# iotchair_nano-shield.net
KiCad netlist of a schematic drawn in EAGLE
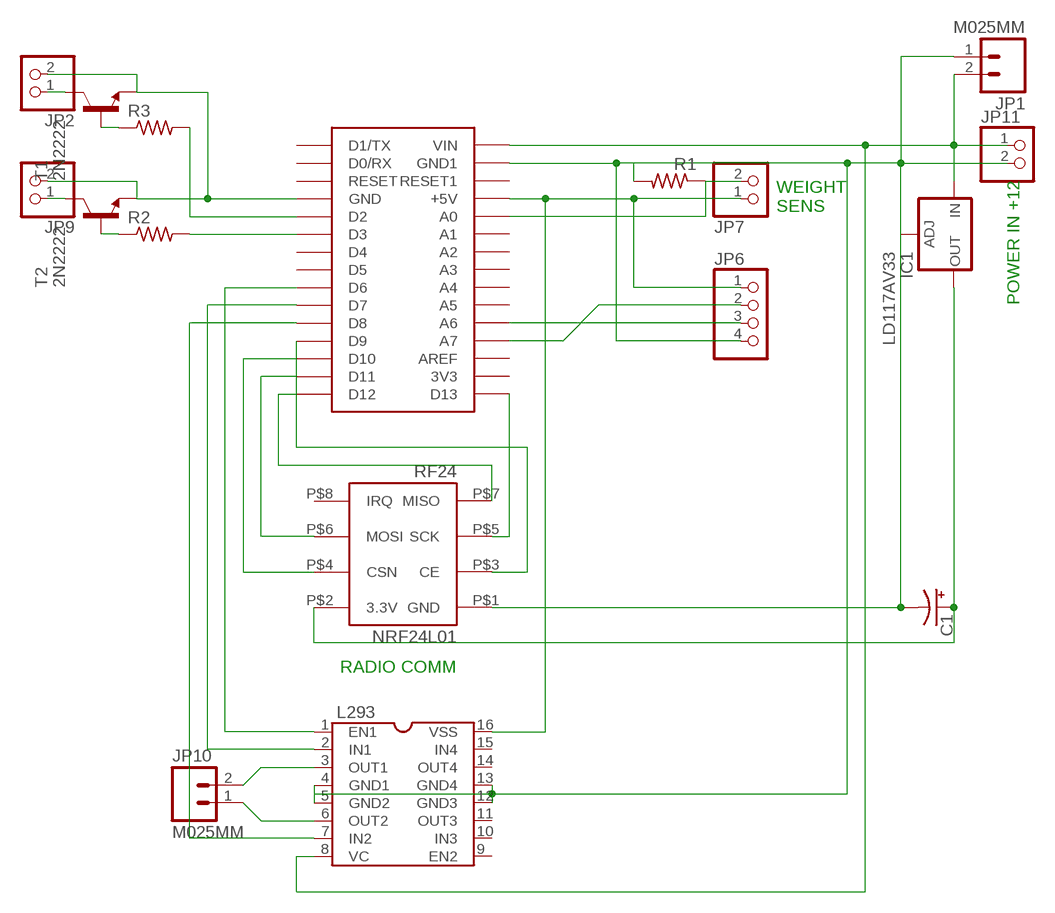
[diagram p0: schematic, sheet 1]

(export (version "E")
  (design (tool "Eeschema 10.0.6"))
  (components
    (comp (ref "C1")
      (value "CPOL-USTT2D6L")
      (footprint "eagle-import:TT2D6L")
      (libsource (lib "eagle-import") (part "CPOL-USTT2D6L"))
    )
    (comp (ref "IC1")
      (value "LD117AV33")
      (footprint "eagle-import:TO220L1")
      (libsource (lib "eagle-import") (part "LD117A?V33"))
    )
    (comp (ref "JP1")
      (value "M025MM")
      (footprint "eagle-import:SCREWTERMINAL-5MM-2")
      (libsource (lib "eagle-import") (part "M025MM"))
    )
    (comp (ref "JP2")
      (value "PINHD-1X2")
      (footprint "eagle-import:1X02")
      (libsource (lib "eagle-import") (part "PINHD-1X2"))
    )
    (comp (ref "JP6")
      (value "PINHD-1X4")
      (footprint "eagle-import:1X04")
      (libsource (lib "eagle-import") (part "PINHD-1X4"))
    )
    (comp (ref "JP7")
      (value "PINHD-1X2")
      (footprint "eagle-import:1X02")
      (libsource (lib "eagle-import") (part "PINHD-1X2"))
    )
    (comp (ref "JP9")
      (value "PINHD-1X2")
      (footprint "eagle-import:1X02")
      (libsource (lib "eagle-import") (part "PINHD-1X2"))
    )
    (comp (ref "JP10")
      (value "M025MM")
      (footprint "eagle-import:SCREWTERMINAL-5MM-2")
      (libsource (lib "eagle-import") (part "M025MM"))
    )
    (comp (ref "JP11")
      (value "PINHD-1X2")
      (footprint "eagle-import:1X02")
      (libsource (lib "eagle-import") (part "PINHD-1X2"))
    )
    (comp (ref "L293")
      (value "DIL16")
      (footprint "eagle-import:DIL16")
      (libsource (lib "eagle-import") (part "DIL16"))
    )
    (comp (ref "NRF24L01")
      (value "RF24")
      (footprint "eagle-import:4X2HEADER")
      (libsource (lib "eagle-import") (part "RF24"))
    )
    (comp (ref "R1")
      (value "R-US_0204/5")
      (footprint "eagle-import:0204_5")
      (libsource (lib "eagle-import") (part "R-US_0204/5"))
    )
    (comp (ref "R2")
      (value "R-US_0204/5")
      (footprint "eagle-import:0204_5")
      (libsource (lib "eagle-import") (part "R-US_0204/5"))
    )
    (comp (ref "R3")
      (value "R-US_0204/5")
      (footprint "eagle-import:0204_5")
      (libsource (lib "eagle-import") (part "R-US_0204/5"))
    )
    (comp (ref "T1")
      (value "2N2222")
      (footprint "eagle-import:TO92-EBC-OVAL")
      (libsource (lib "eagle-import") (part "2N2222"))
    )
    (comp (ref "T2")
      (value "2N2222")
      (footprint "eagle-import:TO92-EBC-OVAL")
      (libsource (lib "eagle-import") (part "2N2222"))
    )
    (comp (ref "U$1")
      (value "ARDUINONANO")
      (footprint "eagle-import:PDIP-32")
      (libsource (lib "eagle-import") (part "ARDUINONANO"))
    )
  )
  (nets
    (net (code "1") (name "Net-(IC1-ADJ)") (class "Default")
      (node (ref "C1") (pin "-") (pinfunction "-_-") (pintype "passive"))
      (node (ref "IC1") (pin "1") (pinfunction "ADJ_1") (pintype "input"))
      (node (ref "JP1") (pin "1") (pinfunction "1_1") (pintype "passive"))
      (node (ref "JP11") (pin "2") (pinfunction "2_2") (pintype "passive"))
      (node (ref "JP6") (pin "4") (pinfunction "4_4") (pintype "passive"))
      (node (ref "L293") (pin "12") (pinfunction "GND3_12") (pintype "passive"))
      (node (ref "L293") (pin "13") (pinfunction "GND4_13") (pintype "passive"))
      (node (ref "L293") (pin "4") (pinfunction "GND1_4") (pintype "passive"))
      (node (ref "L293") (pin "5") (pinfunction "GND2_5") (pintype "passive"))
      (node (ref "NRF24L01") (pin "P$1") (pinfunction "GND_P$1") (pintype "bidirectional"))
      (node (ref "R1") (pin "2") (pinfunction "2_2") (pintype "passive"))
      (node (ref "U$1") (pin "GND1") (pinfunction "GND1_GND1") (pintype "bidirectional"))
    )
    (net (code "2") (name "Net-(IC1-IN)") (class "Default")
      (node (ref "IC1") (pin "3") (pinfunction "IN_3") (pintype "input"))
      (node (ref "JP1") (pin "2") (pinfunction "2_2") (pintype "passive"))
      (node (ref "JP11") (pin "1") (pinfunction "1_1") (pintype "passive"))
      (node (ref "L293") (pin "8") (pinfunction "VC_8") (pintype "passive"))
      (node (ref "U$1") (pin "VIN") (pinfunction "VIN_VIN") (pintype "bidirectional"))
    )
    (net (code "3") (name "Net-(IC1-OUT)") (class "Default")
      (node (ref "C1") (pin "+") (pinfunction "+_+") (pintype "passive"))
      (node (ref "IC1") (pin "2") (pinfunction "OUT_2") (pintype "passive"))
      (node (ref "NRF24L01") (pin "P$2") (pinfunction "3.3V_P$2") (pintype "bidirectional"))
    )
    (net (code "4") (name "Net-(JP2-Pad1)") (class "Default")
      (node (ref "JP2") (pin "1") (pinfunction "1_1") (pintype "passive"))
      (node (ref "T1") (pin "C") (pinfunction "C_C") (pintype "passive"))
    )
    (net (code "5") (name "Net-(JP2-Pad2)") (class "Default")
      (node (ref "JP2") (pin "2") (pinfunction "2_2") (pintype "passive"))
      (node (ref "JP9") (pin "2") (pinfunction "2_2") (pintype "passive"))
      (node (ref "T1") (pin "E") (pinfunction "E_E") (pintype "passive"))
      (node (ref "T2") (pin "E") (pinfunction "E_E") (pintype "passive"))
      (node (ref "U$1") (pin "GND") (pinfunction "GND_GND") (pintype "bidirectional"))
    )
    (net (code "6") (name "Net-(JP6-Pad2)") (class "Default")
      (node (ref "JP6") (pin "2") (pinfunction "2_2") (pintype "passive"))
      (node (ref "U$1") (pin "A7") (pinfunction "A7_A7") (pintype "bidirectional"))
    )
    (net (code "7") (name "Net-(JP6-Pad3)") (class "Default")
      (node (ref "JP6") (pin "3") (pinfunction "3_3") (pintype "passive"))
      (node (ref "U$1") (pin "A6") (pinfunction "A6_A6") (pintype "bidirectional"))
    )
    (net (code "8") (name "Net-(JP7-Pad2)") (class "Default")
      (node (ref "JP7") (pin "2") (pinfunction "2_2") (pintype "passive"))
      (node (ref "R1") (pin "1") (pinfunction "1_1") (pintype "passive"))
      (node (ref "U$1") (pin "A0") (pinfunction "A0_A0") (pintype "bidirectional"))
    )
    (net (code "9") (name "Net-(JP9-Pad1)") (class "Default")
      (node (ref "JP9") (pin "1") (pinfunction "1_1") (pintype "passive"))
      (node (ref "T2") (pin "C") (pinfunction "C_C") (pintype "passive"))
    )
    (net (code "10") (name "Net-(L293-EN1)") (class "Default")
      (node (ref "L293") (pin "1") (pinfunction "EN1_1") (pintype "passive"))
      (node (ref "U$1") (pin "D6") (pinfunction "D6_D6") (pintype "bidirectional"))
    )
    (net (code "11") (name "Net-(L293-IN1)") (class "Default")
      (node (ref "L293") (pin "2") (pinfunction "IN1_2") (pintype "passive"))
      (node (ref "U$1") (pin "D7") (pinfunction "D7_D7") (pintype "bidirectional"))
    )
    (net (code "12") (name "Net-(L293-IN2)") (class "Default")
      (node (ref "L293") (pin "7") (pinfunction "IN2_7") (pintype "passive"))
      (node (ref "U$1") (pin "D8") (pinfunction "D8_D8") (pintype "bidirectional"))
    )
    (net (code "13") (name "Net-(L293-OUT1)") (class "Default")
      (node (ref "JP10") (pin "2") (pinfunction "2_2") (pintype "passive"))
      (node (ref "L293") (pin "3") (pinfunction "OUT1_3") (pintype "passive"))
    )
    (net (code "14") (name "Net-(L293-OUT2)") (class "Default")
      (node (ref "JP10") (pin "1") (pinfunction "1_1") (pintype "passive"))
      (node (ref "L293") (pin "6") (pinfunction "OUT2_6") (pintype "passive"))
    )
    (net (code "15") (name "Net-(L293-VSS)") (class "Default")
      (node (ref "JP6") (pin "1") (pinfunction "1_1") (pintype "passive"))
      (node (ref "JP7") (pin "1") (pinfunction "1_1") (pintype "passive"))
      (node (ref "L293") (pin "16") (pinfunction "VSS_16") (pintype "passive"))
      (node (ref "U$1") (pin "+5V") (pinfunction "+5V_+5V") (pintype "bidirectional"))
    )
    (net (code "16") (name "Net-(NRF24L01-CE)") (class "Default")
      (node (ref "NRF24L01") (pin "P$3") (pinfunction "CE_P$3") (pintype "bidirectional"))
      (node (ref "U$1") (pin "D9") (pinfunction "D9_D9") (pintype "bidirectional"))
    )
    (net (code "17") (name "Net-(NRF24L01-CSN)") (class "Default")
      (node (ref "NRF24L01") (pin "P$4") (pinfunction "CSN_P$4") (pintype "bidirectional"))
      (node (ref "U$1") (pin "D10") (pinfunction "D10_D10") (pintype "bidirectional"))
    )
    (net (code "18") (name "Net-(NRF24L01-MISO)") (class "Default")
      (node (ref "NRF24L01") (pin "P$7") (pinfunction "MISO_P$7") (pintype "bidirectional"))
      (node (ref "U$1") (pin "D12") (pinfunction "D12_D12") (pintype "bidirectional"))
    )
    (net (code "19") (name "Net-(NRF24L01-MOSI)") (class "Default")
      (node (ref "NRF24L01") (pin "P$6") (pinfunction "MOSI_P$6") (pintype "bidirectional"))
      (node (ref "U$1") (pin "D11") (pinfunction "D11_D11") (pintype "bidirectional"))
    )
    (net (code "20") (name "Net-(NRF24L01-SCK)") (class "Default")
      (node (ref "NRF24L01") (pin "P$5") (pinfunction "SCK_P$5") (pintype "bidirectional"))
      (node (ref "U$1") (pin "D13") (pinfunction "D13_D13") (pintype "bidirectional"))
    )
    (net (code "21") (name "Net-(R2-Pad1)") (class "Default")
      (node (ref "R2") (pin "1") (pinfunction "1_1") (pintype "passive"))
      (node (ref "T2") (pin "B") (pinfunction "B_B") (pintype "passive"))
    )
    (net (code "22") (name "Net-(R2-Pad2)") (class "Default")
      (node (ref "R2") (pin "2") (pinfunction "2_2") (pintype "passive"))
      (node (ref "U$1") (pin "D3") (pinfunction "D3_D3") (pintype "bidirectional"))
    )
    (net (code "23") (name "Net-(R3-Pad1)") (class "Default")
      (node (ref "R3") (pin "1") (pinfunction "1_1") (pintype "passive"))
      (node (ref "T1") (pin "B") (pinfunction "B_B") (pintype "passive"))
    )
    (net (code "24") (name "Net-(R3-Pad2)") (class "Default")
      (node (ref "R3") (pin "2") (pinfunction "2_2") (pintype "passive"))
      (node (ref "U$1") (pin "D2") (pinfunction "D2_D2") (pintype "bidirectional"))
    )
    (net (code "25") (name "unconnected-(L293-EN2-Pad9)") (class "Default")
      (node (ref "L293") (pin "9") (pinfunction "EN2_9") (pintype "passive"))
    )
    (net (code "26") (name "unconnected-(L293-IN3-Pad10)") (class "Default")
      (node (ref "L293") (pin "10") (pinfunction "IN3_10") (pintype "passive"))
    )
    (net (code "27") (name "unconnected-(L293-IN4-Pad15)") (class "Default")
      (node (ref "L293") (pin "15") (pinfunction "IN4_15") (pintype "passive"))
    )
    (net (code "28") (name "unconnected-(L293-OUT3-Pad11)") (class "Default")
      (node (ref "L293") (pin "11") (pinfunction "OUT3_11") (pintype "passive"))
    )
    (net (code "29") (name "unconnected-(L293-OUT4-Pad14)") (class "Default")
      (node (ref "L293") (pin "14") (pinfunction "OUT4_14") (pintype "passive"))
    )
    (net (code "30") (name "unconnected-(NRF24L01-IRQ-PadP$8)") (class "Default")
      (node (ref "NRF24L01") (pin "P$8") (pinfunction "IRQ_P$8") (pintype "bidirectional"))
    )
    (net (code "31") (name "unconnected-(U$1-Pad3V3)") (class "Default")
      (node (ref "U$1") (pin "3V3") (pinfunction "3V3_3V3") (pintype "bidirectional"))
    )
    (net (code "32") (name "unconnected-(U$1-PadA1)") (class "Default")
      (node (ref "U$1") (pin "A1") (pinfunction "A1_A1") (pintype "bidirectional"))
    )
    (net (code "33") (name "unconnected-(U$1-PadA2)") (class "Default")
      (node (ref "U$1") (pin "A2") (pinfunction "A2_A2") (pintype "bidirectional"))
    )
    (net (code "34") (name "unconnected-(U$1-PadA3)") (class "Default")
      (node (ref "U$1") (pin "A3") (pinfunction "A3_A3") (pintype "bidirectional"))
    )
    (net (code "35") (name "unconnected-(U$1-PadA4)") (class "Default")
      (node (ref "U$1") (pin "A4") (pinfunction "A4_A4") (pintype "bidirectional"))
    )
    (net (code "36") (name "unconnected-(U$1-PadA5)") (class "Default")
      (node (ref "U$1") (pin "A5") (pinfunction "A5_A5") (pintype "bidirectional"))
    )
    (net (code "37") (name "unconnected-(U$1-PadAREF)") (class "Default")
      (node (ref "U$1") (pin "AREF") (pinfunction "AREF_AREF") (pintype "bidirectional"))
    )
    (net (code "38") (name "unconnected-(U$1-PadD0{slash}RX)") (class "Default")
      (node (ref "U$1") (pin "D0/RX") (pinfunction "D0/RX_D0/RX") (pintype "bidirectional"))
    )
    (net (code "39") (name "unconnected-(U$1-PadD1{slash}TX)") (class "Default")
      (node (ref "U$1") (pin "D1/TX") (pinfunction "D1/TX_D1/TX") (pintype "bidirectional"))
    )
    (net (code "40") (name "unconnected-(U$1-PadD4)") (class "Default")
      (node (ref "U$1") (pin "D4") (pinfunction "D4_D4") (pintype "bidirectional"))
    )
    (net (code "41") (name "unconnected-(U$1-PadD5)") (class "Default")
      (node (ref "U$1") (pin "D5") (pinfunction "D5_D5") (pintype "bidirectional"))
    )
    (net (code "42") (name "unconnected-(U$1-PadRESET)") (class "Default")
      (node (ref "U$1") (pin "RESET") (pinfunction "RESET_RESET") (pintype "bidirectional"))
    )
    (net (code "43") (name "unconnected-(U$1-PadRESET1)") (class "Default")
      (node (ref "U$1") (pin "RESET1") (pinfunction "RESET1_RESET1") (pintype "bidirectional"))
    )
  )
)
